# design.net
KiCad netlist of a schematic drawn in Altium Designer
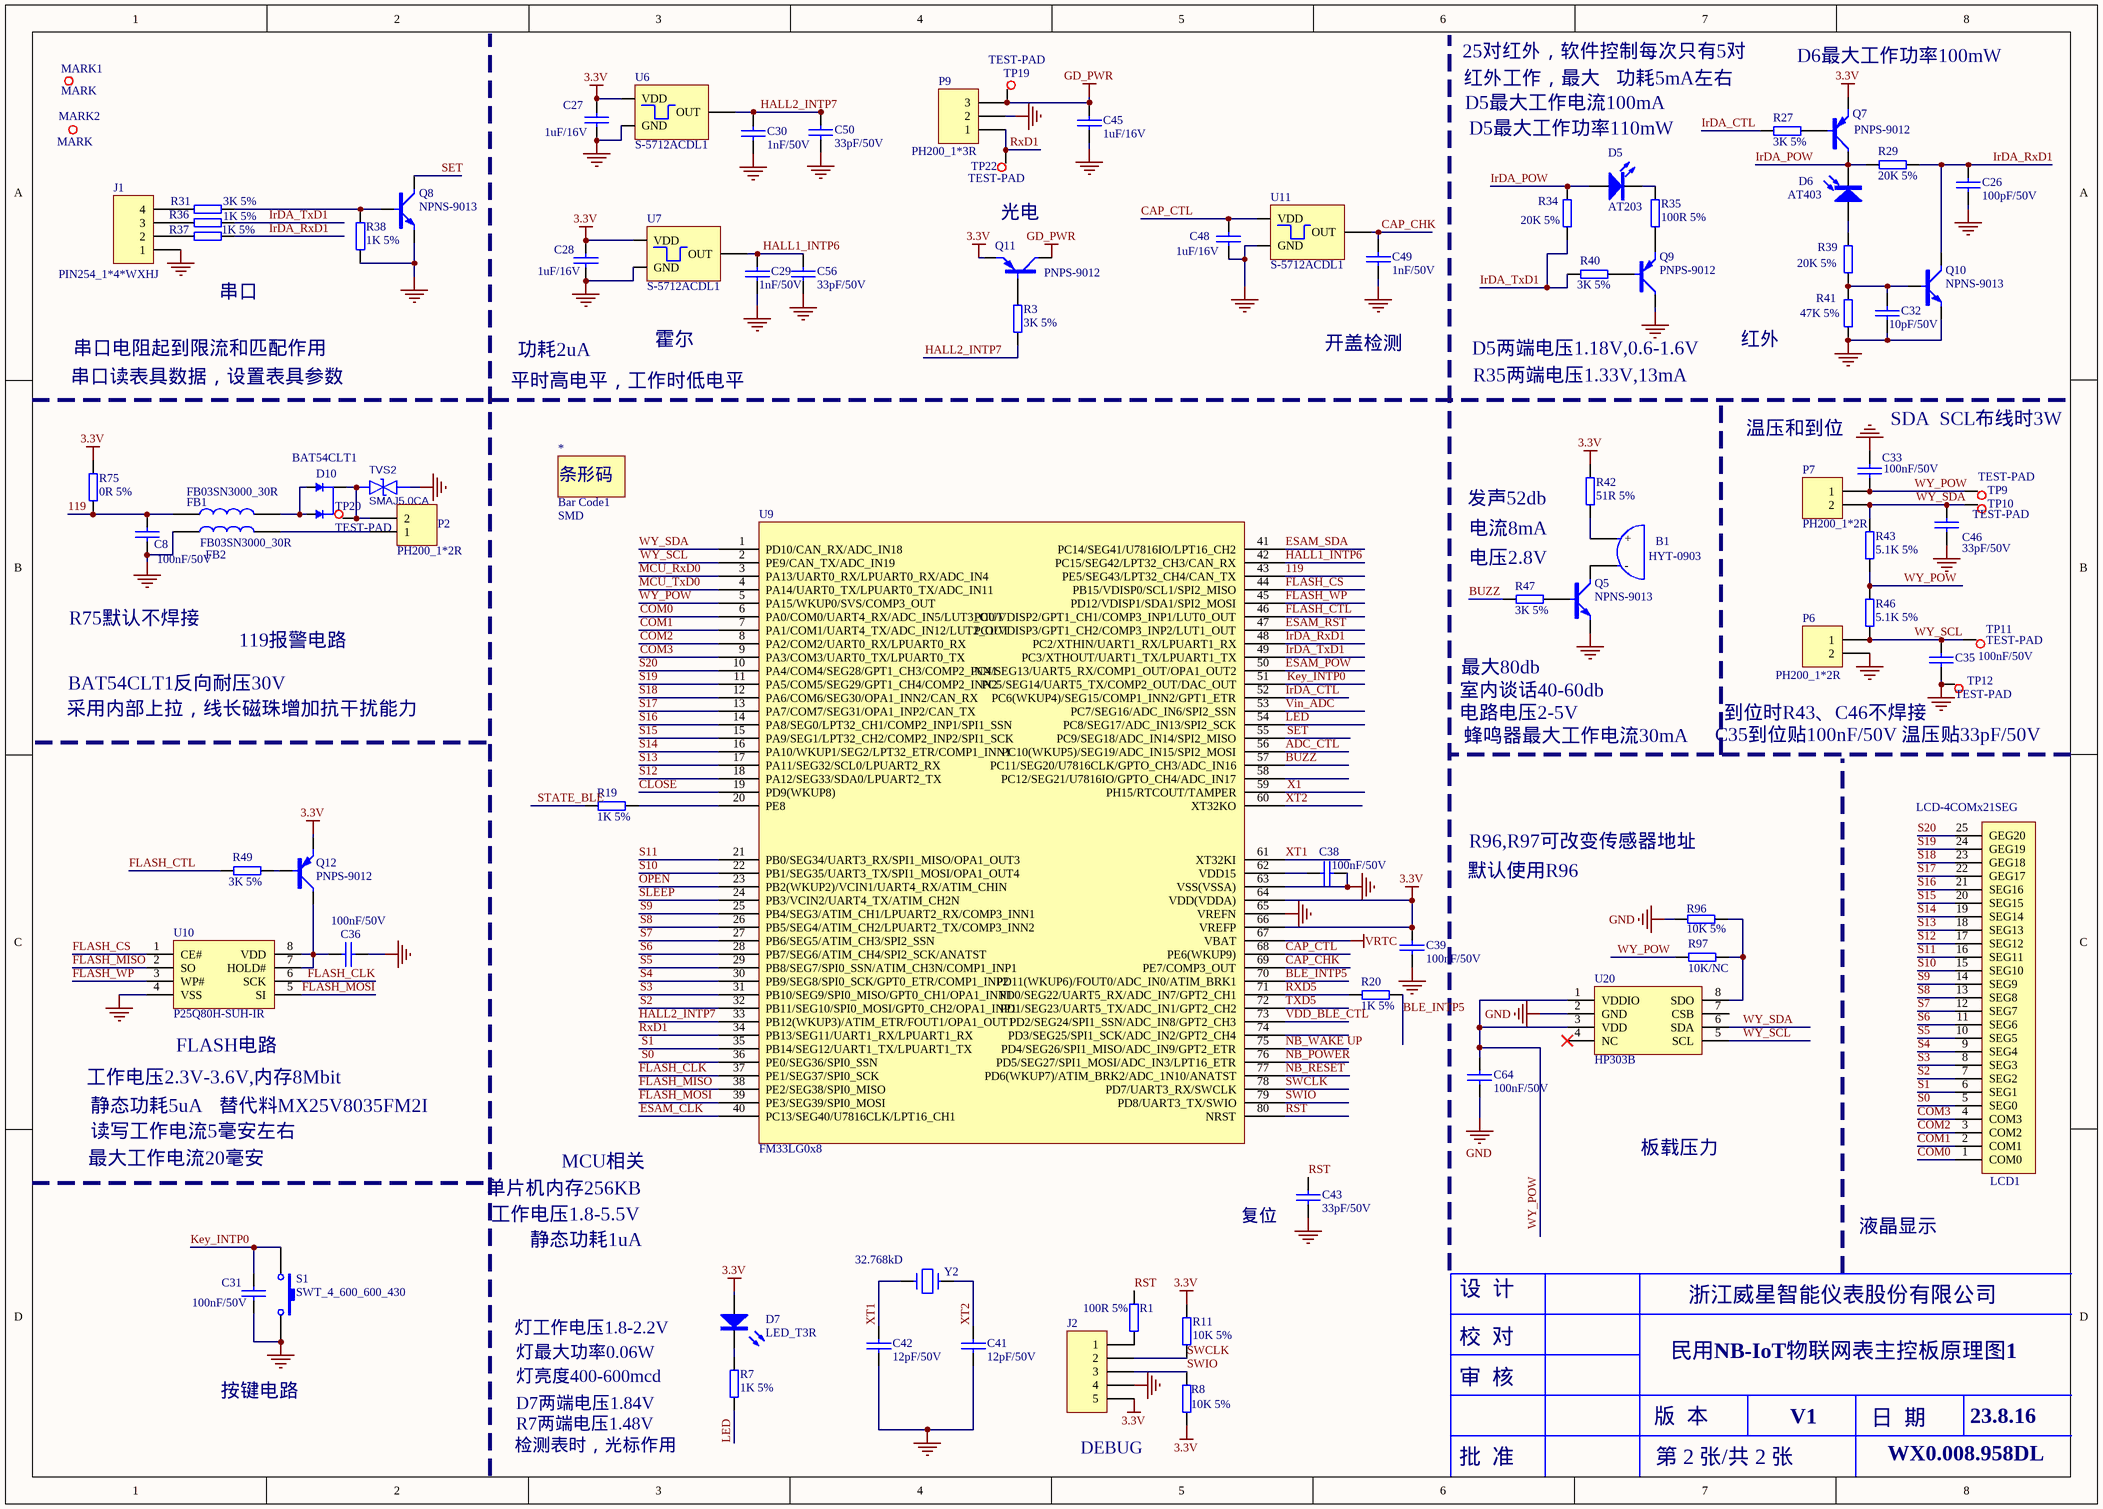
[diagram p0: 主控板.SchDoc]

(export (version "E")
  (design (tool "Eeschema 10.0.6"))
  (components
    (comp (ref "*")
      (value "Bar Code1")
      (footprint "Bar Code1")
      (description "条形码 ,填充，无需焊接器件")
      (fields (field (name "PART NUMBER") "AD_WXHJ_Bar Code_02") (field (name "SMD/DIP") "SMD"))
      (libsource (lib "Database_Libs2") (part "05_AD_WXHJ_Bar Code_02"))
    )
    (comp (ref "B1")
      (value "HYT-0903")
      (footprint "HYT-0903")
      (description "直插,直径9mm,高5.5mm,5 V,2 V,30 mA,兴化市华宇电子有限公司,HYT-0903")
      (fields (field (name "PART NUMBER") "1010602-0007"))
      (libsource (lib "Database_Libs2") (part "07_HYT-0903"))
    )
    (comp (ref "C8")
      (value "100nF/50V")
      (footprint "CAP0603")
      (description "104pF,50 V,±10%,0603,国巨,CC0603KRX7R9BB104")
      (fields (field (name "PART NUMBER") "101020103-0021"))
      (libsource (lib "Database_Libs2") (part "CC03K7R9_100N"))
    )
    (comp (ref "C26")
      (value "100pF/50V")
      (footprint "CAP0603")
      (description "101pf,50 V,±5%,0603,国巨,CC0603JRNP09BN101")
      (fields (field (name "PART NUMBER") "101020103-0010"))
      (libsource (lib "Database_Libs2") (part "CC03JPO9_101P"))
    )
    (comp (ref "C27")
      (value "1uF/16V")
      (footprint "CAP0603")
      (description "105pF,16 V,±10%,0603,国巨,CC0603KRX7R7BB105")
      (fields (field (name "PART NUMBER") "101020103-0003"))
      (libsource (lib "Database_Libs2") (part "CC03K7R7_1U"))
    )
    (comp (ref "C28")
      (value "1uF/16V")
      (footprint "CAP0603")
      (description "105pF,16 V,±10%,0603,国巨,CC0603KRX7R7BB105")
      (fields (field (name "PART NUMBER") "101020103-0003"))
      (libsource (lib "Database_Libs2") (part "CC03K7R7_1U"))
    )
    (comp (ref "C29")
      (value "1nF/50V")
      (footprint "CAP0603")
      (description "102pF,50 V,±10%,0603,国巨,CC0603KRX7R9BB102")
      (fields (field (name "PART NUMBER") "101020103-0022"))
      (libsource (lib "Database_Libs2") (part "CC03K7R9_1N"))
    )
    (comp (ref "C30")
      (value "1nF/50V")
      (footprint "CAP0603")
      (description "102pF,50 V,±10%,0603,国巨,CC0603KRX7R9BB102")
      (fields (field (name "PART NUMBER") "101020103-0022"))
      (libsource (lib "Database_Libs2") (part "CC03K7R9_1N"))
    )
    (comp (ref "C31")
      (value "100nF/50V")
      (footprint "CAP0603")
      (description "104pF,50 V,±10%,0603,国巨,CC0603KRX7R9BB104")
      (fields (field (name "PART NUMBER") "101020103-0021"))
      (libsource (lib "Database_Libs2") (part "CC03K7R9_100N"))
    )
    (comp (ref "C32")
      (value "10pF/50V")
      (footprint "CAP0603")
      (description "10pF,50 V,±5%,0603,X7R,国巨,CC0603JRNPO9BN100")
      (fields (field (name "PART NUMBER") "101020103-0014"))
      (libsource (lib "Database_Libs2") (part "CC03JPO9_10P"))
    )
    (comp (ref "C33")
      (value "100nF/50V")
      (footprint "CAP0603")
      (description "104pF,50 V,±10%,0603,国巨,CC0603KRX7R9BB104")
      (fields (field (name "PART NUMBER") "101020103-0021"))
      (libsource (lib "Database_Libs2") (part "CC03K7R9_100N"))
    )
    (comp (ref "C35")
      (value "100nF/50V")
      (footprint "CAP0603")
      (description "104pF,50 V,±10%,0603,国巨,CC0603KRX7R9BB104")
      (fields (field (name "PART NUMBER") "101020103-0021"))
      (libsource (lib "Database_Libs2") (part "CC03K7R9_100N"))
    )
    (comp (ref "C36")
      (value "100nF/50V")
      (footprint "CAP0603")
      (description "104pF,50 V,±10%,0603,国巨,CC0603KRX7R9BB104")
      (fields (field (name "PART NUMBER") "101020103-0021"))
      (libsource (lib "Database_Libs2") (part "CC03K7R9_100N"))
    )
    (comp (ref "C38")
      (value "100nF/50V")
      (footprint "CAP0603")
      (description "104pF,50 V,±10%,0603,国巨,CC0603KRX7R9BB104")
      (fields (field (name "PART NUMBER") "101020103-0021"))
      (libsource (lib "Database_Libs2") (part "CC03K7R9_100N"))
    )
    (comp (ref "C39")
      (value "100nF/50V")
      (footprint "CAP0603")
      (description "104pF,50 V,±10%,0603,国巨,CC0603KRX7R9BB104")
      (fields (field (name "PART NUMBER") "101020103-0021"))
      (libsource (lib "Database_Libs2") (part "CC03K7R9_100N"))
    )
    (comp (ref "C41")
      (value "12pF/50V")
      (footprint "CAP0603")
      (description "12P,50 V,±5%,0603,国巨,CC0603JRNPO9BN12")
      (fields (field (name "PART NUMBER") "101020103-0005"))
      (libsource (lib "Database_Libs2") (part "CC03JPO9_12P"))
    )
    (comp (ref "C42")
      (value "12pF/50V")
      (footprint "CAP0603")
      (description "12P,50 V,±5%,0603,国巨,CC0603JRNPO9BN12")
      (fields (field (name "PART NUMBER") "101020103-0005"))
      (libsource (lib "Database_Libs2") (part "CC03JPO9_12P"))
    )
    (comp (ref "C43")
      (value "33pF/50V")
      (footprint "CAP0603")
      (description "33pF,50 V,±10%,0603,国巨,CC0603KRNPO9BN33")
      (fields (field (name "PART NUMBER") "101020103-0027"))
      (libsource (lib "Database_Libs2") (part "CC03KPO9_33P"))
    )
    (comp (ref "C45")
      (value "1uF/16V")
      (footprint "CAP0603")
      (description "105pF,16 V,±10%,0603,国巨,CC0603KRX7R7BB105")
      (fields (field (name "PART NUMBER") "101020103-0003"))
      (libsource (lib "Database_Libs2") (part "CC03K7R7_1U"))
    )
    (comp (ref "C46")
      (value "33pF/50V")
      (footprint "CAP0603")
      (description "33pF,50 V,±10%,0603,国巨,CC0603KRNPO9BN33")
      (fields (field (name "PART NUMBER") "101020103-0027"))
      (libsource (lib "Database_Libs2") (part "CC03KPO9_33P"))
    )
    (comp (ref "C48")
      (value "1uF/16V")
      (footprint "CAP0603")
      (description "105pF,16 V,±10%,0603,国巨,CC0603KRX7R7BB105")
      (fields (field (name "PART NUMBER") "101020103-0003"))
      (libsource (lib "Database_Libs2") (part "CC03K7R7_1U"))
    )
    (comp (ref "C49")
      (value "1nF/50V")
      (footprint "CAP0603")
      (description "102pF,50 V,±10%,0603,国巨,CC0603KRX7R9BB102")
      (fields (field (name "PART NUMBER") "101020103-0022"))
      (libsource (lib "Database_Libs2") (part "CC03K7R9_1N"))
    )
    (comp (ref "C50")
      (value "33pF/50V")
      (footprint "CAP0603")
      (description "33pF,50 V,±10%,0603,国巨,CC0603KRNPO9BN33")
      (fields (field (name "PART NUMBER") "101020103-0027"))
      (libsource (lib "Database_Libs2") (part "CC03KPO9_33P"))
    )
    (comp (ref "C56")
      (value "33pF/50V")
      (footprint "CAP0603")
      (description "33pF,50 V,±10%,0603,国巨,CC0603KRNPO9BN33")
      (fields (field (name "PART NUMBER") "101020103-0027"))
      (libsource (lib "Database_Libs2") (part "CC03KPO9_33P"))
    )
    (comp (ref "C64")
      (value "100nF/50V")
      (footprint "CAP0603")
      (description "104pF,50 V,±10%,0603,国巨,CC0603KRX7R9BB104")
      (fields (field (name "PART NUMBER") "101020103-0021"))
      (libsource (lib "Database_Libs2") (part "CC03K7R9_100N"))
    )
    (comp (ref "D5")
      (value "AT203")
      (footprint "IR_254_532_300")
      (description "DIP-2,φ3,插件,红光,上海品观电子有限公司/可得,AT203")
      (fields (field (name "PART NUMBER") "101040102-0010"))
      (libsource (lib "Database_Libs2") (part "01_AT203"))
    )
    (comp (ref "D6")
      (value "AT403")
      (footprint "IR_254_532_300")
      (description "DIP-2,φ3,插件,红光,上海品观电子有限公司/可得,AT403-PD-01")
      (fields (field (name "PART NUMBER") "101040102-0011"))
      (libsource (lib "Database_Libs2") (part "01_AT403"))
    )
    (comp (ref "D7")
      (value "LED_T3R")
      (footprint "LED2_300")
      (description "圆形插件,3mm 圆形,插件,红光,湖北匡通电子有限公司,3BB4HC")
      (fields (field (name "PART NUMBER") "101040102-0001"))
      (libsource (lib "Database_Libs2") (part "01-LED_T3R"))
    )
    (comp (ref "D10")
      (value "BAT54CLT1")
      (footprint "SOT-23")
      (description "BAT54CLT1，SOT23-3,SOT23-3,0.2 A,0.8 V,30 V,安森美,BAT54CLT1")
      (fields (field (name "PART NUMBER") "101040101-0038"))
      (libsource (lib "Database_Libs2") (part "02_BAT54CLT1"))
    )
    (comp (ref "FB1")
      (value "FB03SN3000_30R")
      (footprint "IND0603")
      (description "chilisin(奇力新),0603,30Ω ±25% @100MHz,150 V,125 ℃,PBY160808T-300Y-N,-55 ℃,不含铅,,,圆盘,30Ω ±25% @100MHz")
      (fields (field (name "PART NUMBER") "109010101-0003"))
      (libsource (lib "Database_Libs2") (part "06_FB03SN3000_30R"))
    )
    (comp (ref "FB2")
      (value "FB03SN3000_30R")
      (footprint "IND0603")
      (description "chilisin(奇力新),0603,30Ω ±25% @100MHz,150 V,125 ℃,PBY160808T-300Y-N,-55 ℃,不含铅,,,圆盘,30Ω ±25% @100MHz")
      (fields (field (name "PART NUMBER") "109010101-0003"))
      (libsource (lib "Database_Libs2") (part "06_FB03SN3000_30R"))
    )
    (comp (ref "J1")
      (value "PIN254_1*4*WXHJ")
      (footprint "PIN254_1*4*WXHJ")
      (description "1*4 ，Φ1.0 ，2.54mm，直脚,无需焊接器件")
      (fields (field (name "PART NUMBER") "AD_WXHJ_PinHeader_01"))
      (libsource (lib "Database_Libs2") (part "PIN254_1*4*WXHJ"))
    )
    (comp (ref "J2")
      (value "PIN254_1*5*WXHJ")
      (footprint "PIN254_1*5*WXHJ")
      (description "1*5 ，Φ1.0 ，2.54mm，直脚,无需焊接器件")
      (fields (field (name "PART NUMBER") "AD_WXHJ_PinHeader_02"))
      (libsource (lib "Database_Libs2") (part "PIN254_1*5*WXHJ"))
    )
    (comp (ref "LCD1")
      (value "GVH21861A-HPP")
      (footprint "LCD_GVH21861A-HPP")
      (fields (field (name "PART NUMBER") "1010801-0028") (field (name "SMD/DIP") "LCD-4COMx21SEG"))
      (libsource (lib "Database_Libs2") (part "03_LCD_GVH21861A-HPP"))
    )
    (comp (ref "MARK1")
      (value "MARK")
      (footprint "MARK")
      (description "MARK点")
      (fields (field (name "PART NUMBER") "AD_WXHJ_MARK_01"))
      (libsource (lib "Database_Libs2") (part "MARK"))
    )
    (comp (ref "MARK2")
      (value "MARK")
      (footprint "MARK")
      (description "MARK点")
      (fields (field (name "PART NUMBER") "AD_WXHJ_MARK_01"))
      (libsource (lib "Database_Libs2") (part "MARK"))
    )
    (comp (ref "P2")
      (value "PH200_1*2R")
      (footprint "PH200_1*2R")
      (description "2.0-2AW,直插弯座，2PIN，脚间距2mm，带防翘起,公头,单排,2.0-2AW;直插弯座，2PIN,脚间距2mm，带防翘起")
      (fields (field (name "PART NUMBER") "1010902-0105"))
      (libsource (lib "Database_Libs2") (part "PH200_1*2R"))
    )
    (comp (ref "P6")
      (value "PH200_1*2R")
      (footprint "PH200_1*2R")
      (description "2.0-2AW,直插弯座，2PIN，脚间距2mm，带防翘起,公头,单排,2.0-2AW;直插弯座，2PIN,脚间距2mm，带防翘起")
      (fields (field (name "PART NUMBER") "1010902-0105"))
      (libsource (lib "") (part "PH200_1*2R_1"))
    )
    (comp (ref "P7")
      (value "PH200_1*2R")
      (footprint "PH200_1*2R")
      (description "2.0-2AW,直插弯座，2PIN，脚间距2mm，带防翘起,公头,单排,2.0-2AW;直插弯座，2PIN,脚间距2mm，带防翘起")
      (fields (field (name "PART NUMBER") "1010902-0105"))
      (libsource (lib "") (part "PH200_1*2R_1"))
    )
    (comp (ref "P9")
      (value "PH200_1*3R")
      (footprint "PH200_1*3R")
      (description "2.0-3AW,3PIN，2mm脚间距,公头,单排,2.0-3AW；3PIN，脚间距2mm直插弯座带防翘起")
      (fields (field (name "PART NUMBER") "1010902-0104"))
      (libsource (lib "Database_Libs2") (part "PH200_1*3R"))
    )
    (comp (ref "Q5")
      (value "NPNS-9013")
      (footprint "SOT-23")
      (description "9013,NPN,SOT-23,长电,S9013")
      (fields (field (name "PART NUMBER") "101040201-0002"))
      (libsource (lib "Database_Libs2") (part "03_NPNS-9013"))
    )
    (comp (ref "Q7")
      (value "PNPS-9012")
      (footprint "SOT-23")
      (description "9012,PNP,SOT-23,JCET;长电,S9012")
      (fields (field (name "PART NUMBER") "101040201-0001"))
      (libsource (lib "Database_Libs2") (part "03_PNPS-9012"))
    )
    (comp (ref "Q8")
      (value "NPNS-9013")
      (footprint "SOT-23")
      (description "9013,NPN,SOT-23,长电,S9013")
      (fields (field (name "PART NUMBER") "101040201-0002"))
      (libsource (lib "Database_Libs2") (part "03_NPNS-9013"))
    )
    (comp (ref "Q9")
      (value "PNPS-9012")
      (footprint "SOT-23")
      (description "9012,PNP,SOT-23,JCET;长电,S9012")
      (fields (field (name "PART NUMBER") "101040201-0001"))
      (libsource (lib "Database_Libs2") (part "03_PNPS-9012"))
    )
    (comp (ref "Q10")
      (value "NPNS-9013")
      (footprint "SOT-23")
      (description "9013,NPN,SOT-23,长电,S9013")
      (fields (field (name "PART NUMBER") "101040201-0002"))
      (libsource (lib "Database_Libs2") (part "03_NPNS-9013"))
    )
    (comp (ref "Q11")
      (value "PNPS-9012")
      (footprint "SOT-23")
      (description "9012,PNP,SOT-23,JCET;长电,S9012")
      (fields (field (name "PART NUMBER") "101040201-0001"))
      (libsource (lib "Database_Libs2") (part "03_PNPS-9012"))
    )
    (comp (ref "Q12")
      (value "PNPS-9012")
      (footprint "SOT-23")
      (description "9012,PNP,SOT-23,JCET;长电,S9012")
      (fields (field (name "PART NUMBER") "101040201-0001"))
      (libsource (lib "Database_Libs2") (part "03_PNPS-9012"))
    )
    (comp (ref "R1")
      (value "100R 5%")
      (footprint "RES0603")
      (description "100R,±5%,1/10W,0603,国巨,RC0603JR-07100RL")
      (fields (field (name "PART NUMBER") "101010103-0022"))
      (libsource (lib "Database_Libs2") (part "RC03J_100R"))
    )
    (comp (ref "R3")
      (value "3K 5%")
      (footprint "RES0603")
      (description "国巨,±5%,0603,,155 ℃,-55 ℃,RC0603JR-073KL,无铅,100 ppm/℃,1/10W,,3K")
      (fields (field (name "PART NUMBER") "101010103-0006"))
      (libsource (lib "Database_Libs2") (part "RC03J_3K"))
    )
    (comp (ref "R7")
      (value "1K 5%")
      (footprint "RES0603")
      (description "1K,±5%,1/10W,0603,国巨,RC0603JR-071KL")
      (fields (field (name "PART NUMBER") "101010103-0008"))
      (libsource (lib "Database_Libs2") (part "RC03J_1K"))
    )
    (comp (ref "R8")
      (value "10K 5%")
      (footprint "RES0603")
      (description "国巨,±5%,0603,,155 ℃,-55 ℃,RC0603JR-0710KL,无铅,200 ppm/℃,1/10W,,10K")
      (fields (field (name "PART NUMBER") "101010103-0003"))
      (libsource (lib "Database_Libs2") (part "RC03J_10K"))
    )
    (comp (ref "R11")
      (value "10K 5%")
      (footprint "RES0603")
      (description "国巨,±5%,0603,,155 ℃,-55 ℃,RC0603JR-0710KL,无铅,200 ppm/℃,1/10W,,10K")
      (fields (field (name "PART NUMBER") "101010103-0003"))
      (libsource (lib "Database_Libs2") (part "RC03J_10K"))
    )
    (comp (ref "R19")
      (value "1K 5%")
      (footprint "RES0603")
      (description "1K,±5%,1/10W,0603,国巨,RC0603JR-071KL")
      (fields (field (name "PART NUMBER") "101010103-0008"))
      (libsource (lib "Database_Libs2") (part "RC03J_1K"))
    )
    (comp (ref "R20")
      (value "1K 5%")
      (footprint "RES0603")
      (description "1K,±5%,1/10W,0603,国巨,RC0603JR-071KL")
      (fields (field (name "PART NUMBER") "101010103-0008"))
      (libsource (lib "Database_Libs2") (part "RC03J_1K"))
    )
    (comp (ref "R27")
      (value "3K 5%")
      (footprint "RES0603")
      (description "国巨,±5%,0603,,155 ℃,-55 ℃,RC0603JR-073KL,无铅,100 ppm/℃,1/10W,,3K")
      (fields (field (name "PART NUMBER") "101010103-0006"))
      (libsource (lib "Database_Libs2") (part "RC03J_3K"))
    )
    (comp (ref "R29")
      (value "20K 5%")
      (footprint "RES0603")
      (description "国巨,±5%,0603,,155 ℃,-55 ℃,RC0603JR-0720KL,无铅,200 ppm/℃,1/10W,,20K")
      (fields (field (name "PART NUMBER") "101010103-0004"))
      (libsource (lib "Database_Libs2") (part "RC03J_20K"))
    )
    (comp (ref "R31")
      (value "3K 5%")
      (footprint "RES0603")
      (description "国巨,±5%,0603,,155 ℃,-55 ℃,RC0603JR-073KL,无铅,100 ppm/℃,1/10W,,3K")
      (fields (field (name "PART NUMBER") "101010103-0006"))
      (libsource (lib "Database_Libs2") (part "RC03J_3K"))
    )
    (comp (ref "R34")
      (value "20K 5%")
      (footprint "RES0603")
      (description "国巨,±5%,0603,,155 ℃,-55 ℃,RC0603JR-0720KL,无铅,200 ppm/℃,1/10W,,20K")
      (fields (field (name "PART NUMBER") "101010103-0004"))
      (libsource (lib "Database_Libs2") (part "RC03J_20K"))
    )
    (comp (ref "R35")
      (value "100R 5%")
      (footprint "RES0603")
      (description "100R,±5%,1/10W,0603,国巨,RC0603JR-07100RL")
      (fields (field (name "PART NUMBER") "101010103-0022"))
      (libsource (lib "Database_Libs2") (part "RC03J_100R"))
    )
    (comp (ref "R36")
      (value "1K 5%")
      (footprint "RES0603")
      (description "1K,±5%,1/10W,0603,国巨,RC0603JR-071KL")
      (fields (field (name "PART NUMBER") "101010103-0008"))
      (libsource (lib "Database_Libs2") (part "RC03J_1K"))
    )
    (comp (ref "R37")
      (value "1K 5%")
      (footprint "RES0603")
      (description "1K,±5%,1/10W,0603,国巨,RC0603JR-071KL")
      (fields (field (name "PART NUMBER") "101010103-0008"))
      (libsource (lib "Database_Libs2") (part "RC03J_1K"))
    )
    (comp (ref "R38")
      (value "1K 5%")
      (footprint "RES0603")
      (description "1K,±5%,1/10W,0603,国巨,RC0603JR-071KL")
      (fields (field (name "PART NUMBER") "101010103-0008"))
      (libsource (lib "Database_Libs2") (part "RC03J_1K"))
    )
    (comp (ref "R39")
      (value "20K 5%")
      (footprint "RES0603")
      (description "国巨,±5%,0603,,155 ℃,-55 ℃,RC0603JR-0720KL,无铅,200 ppm/℃,1/10W,,20K")
      (fields (field (name "PART NUMBER") "101010103-0004"))
      (libsource (lib "Database_Libs2") (part "RC03J_20K"))
    )
    (comp (ref "R40")
      (value "3K 5%")
      (footprint "RES0603")
      (description "国巨,±5%,0603,,155 ℃,-55 ℃,RC0603JR-073KL,无铅,100 ppm/℃,1/10W,,3K")
      (fields (field (name "PART NUMBER") "101010103-0006"))
      (libsource (lib "Database_Libs2") (part "RC03J_3K"))
    )
    (comp (ref "R41")
      (value "47K 5%")
      (footprint "RES0603")
      (description "47K,±5%,1/10W,0603,国巨,RC0603JR-0747KL")
      (fields (field (name "PART NUMBER") "101010103-0012"))
      (libsource (lib "Database_Libs2") (part "RC03J_47K"))
    )
    (comp (ref "R42")
      (value "51R 5%")
      (footprint "RES0603")
      (description "国巨,±5%,0603,,155 ℃,-55 ℃,RC0603JR-0751RL,无铅,100 ppm/℃,1/10W,,51欧")
      (fields (field (name "PART NUMBER") "101010103-0037"))
      (libsource (lib "Database_Libs2") (part "RC03J_51R"))
    )
    (comp (ref "R43")
      (value "5.1K 5%")
      (footprint "RES0603")
      (description "国巨,±5%,0603,,155 ℃,55 ℃,RC0603JR-075.1KL,无铅,200 ppm/℃,1/10W,,5.1k")
      (fields (field (name "PART NUMBER") "101010103-0015"))
      (libsource (lib "Database_Libs2") (part "RC03J_5.1K"))
    )
    (comp (ref "R46")
      (value "5.1K 5%")
      (footprint "RES0603")
      (description "国巨,±5%,0603,,155 ℃,55 ℃,RC0603JR-075.1KL,无铅,200 ppm/℃,1/10W,,5.1k")
      (fields (field (name "PART NUMBER") "101010103-0015"))
      (libsource (lib "Database_Libs2") (part "RC03J_5.1K"))
    )
    (comp (ref "R47")
      (value "3K 5%")
      (footprint "RES0603")
      (description "国巨,±5%,0603,,155 ℃,-55 ℃,RC0603JR-073KL,无铅,100 ppm/℃,1/10W,,3K")
      (fields (field (name "PART NUMBER") "101010103-0006"))
      (libsource (lib "Database_Libs2") (part "RC03J_3K"))
    )
    (comp (ref "R49")
      (value "3K 5%")
      (footprint "RES0603")
      (description "国巨,±5%,0603,,155 ℃,-55 ℃,RC0603JR-073KL,无铅,100 ppm/℃,1/10W,,3K")
      (fields (field (name "PART NUMBER") "101010103-0006"))
      (libsource (lib "Database_Libs2") (part "RC03J_3K"))
    )
    (comp (ref "R75")
      (value "0R 5%")
      (footprint "RES0603")
      (description "国巨,±5%,0603,,155 ℃,-55 ℃,RC0603J2-070RL,无铅,200 ppm/℃,1/10W,,0R")
      (fields (field (name "PART NUMBER") "101010103-0001"))
      (libsource (lib "Database_Libs2") (part "RC03J_0R"))
    )
    (comp (ref "R96")
      (value "10K 5%")
      (footprint "RES0603")
      (description "国巨,±5%,0603,,155 ℃,-55 ℃,RC0603J2-070RL,无铅,200 ppm/℃,1/10W,,0R")
      (fields (field (name "PART NUMBER") "101010103-0001"))
      (libsource (lib "Database_Libs2") (part "RC03J_0R"))
    )
    (comp (ref "R97")
      (value "10K/NC")
      (footprint "RES0603")
      (description "国巨,±5%,0603,,155 ℃,-55 ℃,RC0603JR-071ML,无铅,200 ppm/℃,1/10W,,1M")
      (libsource (lib "Database_Libs2") (part "RC03J_1M"))
    )
    (comp (ref "S1")
      (value "SWT_4_600_600_430")
      (footprint "SWT_4_600_600")
      (description "TS-1102,机械轻触,6*6*4.3直插,6*6*4.3直插,乐清市羽欧电子")
      (fields (field (name "PART NUMBER") "1011001-0027"))
      (libsource (lib "Database_Libs2") (part "07_SWT_4_600_600_430"))
    )
    (comp (ref "TP9")
      (value "TEST-PAD")
      (footprint "TEST-PAD")
      (description "单面焊盘测试点")
      (fields (field (name "PART NUMBER") "AD_WXHJ_TEST-PAD_01"))
      (libsource (lib "Database_Libs2") (part "TEST-PAD"))
    )
    (comp (ref "TP10")
      (value "TEST-PAD")
      (footprint "TEST-PAD")
      (description "单面焊盘测试点")
      (fields (field (name "PART NUMBER") "AD_WXHJ_TEST-PAD_01"))
      (libsource (lib "Database_Libs2") (part "TEST-PAD"))
    )
    (comp (ref "TP11")
      (value "TEST-PAD")
      (footprint "TEST-PAD")
      (description "单面焊盘测试点")
      (fields (field (name "PART NUMBER") "AD_WXHJ_TEST-PAD_01"))
      (libsource (lib "Database_Libs2") (part "TEST-PAD"))
    )
    (comp (ref "TP12")
      (value "TEST-PAD")
      (footprint "TEST-PAD")
      (description "单面焊盘测试点")
      (fields (field (name "PART NUMBER") "AD_WXHJ_TEST-PAD_01"))
      (libsource (lib "Database_Libs2") (part "TEST-PAD"))
    )
    (comp (ref "TP19")
      (value "TEST-PAD")
      (footprint "TEST-PAD")
      (description "单面焊盘测试点")
      (fields (field (name "PART NUMBER") "AD_WXHJ_TEST-PAD_01"))
      (libsource (lib "Database_Libs2") (part "TEST-PAD"))
    )
    (comp (ref "TP20")
      (value "TEST-PAD")
      (footprint "TEST-PAD")
      (description "单面焊盘测试点")
      (fields (field (name "PART NUMBER") "AD_WXHJ_TEST-PAD_01"))
      (libsource (lib "Database_Libs2") (part "TEST-PAD"))
    )
    (comp (ref "TP22")
      (value "TEST-PAD")
      (footprint "TEST-PAD")
      (description "单面焊盘测试点")
      (fields (field (name "PART NUMBER") "AD_WXHJ_TEST-PAD_01"))
      (libsource (lib "Database_Libs2") (part "TEST-PAD"))
    )
    (comp (ref "TVS2")
      (value "SMAJ5.0CA")
      (footprint "SMAJ5.0CA")
      (fields (field (name "BOM_SUPPLIER PART") "C693487") (field (name "CONTRIBUTOR") "LCSC"))
      (libsource (lib "Discrete_WX") (part "SMAJ5.0CA_C693487"))
    )
    (comp (ref "U6")
      (value "S-5712ACDL1")
      (footprint "SOT-23")
      (description "S-5712ACDL1,SOT23-3,3.5 V,1.6 V,2 uA,精工电子,S-5712ACDL1")
      (fields (field (name "PART NUMBER") "1010504-0002"))
      (libsource (lib "Database_Libs2") (part "01_S-5712ACDL1"))
    )
    (comp (ref "U7")
      (value "S-5712ACDL1")
      (footprint "SOT-23")
      (description "S-5712ACDL1,SOT23-3,3.5 V,1.6 V,2 uA,精工电子,S-5712ACDL1")
      (fields (field (name "PART NUMBER") "1010504-0002"))
      (libsource (lib "Database_Libs2") (part "01_S-5712ACDL1"))
    )
    (comp (ref "U9") (value "FM33LG0x8") (footprint "LQFP80") (libsource (lib "FM_MCU") (part "FM33LG0x8")))
    (comp (ref "U10")
      (value "P25Q80H-SUH-IR")
      (footprint "SOP-8L-200MIL")
      (description "P25Q80H-SUH-IR,SOP8208mil,普冉半导体（上海）股份有限公司,P25Q80H-SUH-IR")
      (fields (field (name "PART NUMBER") "101050101-0218"))
      (libsource (lib "Database_Libs2") (part "04_GD25VQ80CSIG"))
    )
    (comp (ref "U11")
      (value "S-5712ACDL1")
      (footprint "SOT-23")
      (description "S-5712ACDL1,SOT23-3,3.5 V,1.6 V,2 uA,精工电子,S-5712ACDL1")
      (fields (field (name "PART NUMBER") "1010504-0002"))
      (libsource (lib "Database_Libs2") (part "01_S-5712ACDL1"))
    )
    (comp (ref "U20") (value "HP303B") (footprint "LGA_8") (libsource (lib "Schlib2") (part "HP303B")))
    (comp (ref "Y2")
      (value "32.768kD")
      (footprint "SMD-3215_2P")
      (fields (field (name "PART NUMBER") "1010601-0020"))
      (libsource (lib "Database_Libs2") (part "04_XTALSG12MD_32.768kD"))
    )
  )
  (nets
    (net (code "1") (name "/119") (class "Default")
      (node (ref "C8") (pin "1") (pinfunction "1_1") (pintype "passive"))
      (node (ref "FB1") (pin "1") (pinfunction "1_1") (pintype "passive"))
      (node (ref "R75") (pin "2") (pinfunction "2_2") (pintype "passive"))
      (node (ref "U9") (pin "43") (pinfunction "PE5/SEG43/LPT32_CH4/CAN_TX_43") (pintype "passive"))
    )
    (net (code "2") (name "/ADC_CTL") (class "Default")
      (node (ref "U9") (pin "56") (pinfunction "PC10(WKUP5)/SEG19/ADC_IN15/SPI2_MOSI_56") (pintype "passive"))
    )
    (net (code "3") (name "/BLE_INTP5") (class "Default")
      (node (ref "R20") (pin "1") (pinfunction "1_1") (pintype "passive"))
      (node (ref "U9") (pin "70") (pinfunction "PD11(WKUP6)/FOUT0/ADC_IN0/ATIM_BRK1_70") (pintype "passive"))
    )
    (net (code "4") (name "/BUZZ") (class "Default")
      (node (ref "R47") (pin "1") (pinfunction "1_1") (pintype "passive"))
      (node (ref "U9") (pin "57") (pinfunction "PC11/SEG20/U7816CLK/GPTO_CH3/ADC_IN16_57") (pintype "passive"))
    )
    (net (code "5") (name "/CAP_CHK") (class "Default")
      (node (ref "C49") (pin "1") (pinfunction "1_1") (pintype "passive"))
      (node (ref "U11") (pin "2") (pinfunction "OUT_2") (pintype "passive"))
      (node (ref "U9") (pin "69") (pinfunction "PE7/COMP3_OUT_69") (pintype "passive"))
    )
    (net (code "6") (name "/CAP_CTL") (class "Default")
      (node (ref "C48") (pin "1") (pinfunction "1_1") (pintype "passive"))
      (node (ref "U11") (pin "1") (pinfunction "VDD_1") (pintype "passive"))
      (node (ref "U9") (pin "68") (pinfunction "PE6(WKUP9)_68") (pintype "passive"))
    )
    (net (code "7") (name "/CLOSE") (class "Default")
      (node (ref "U9") (pin "19") (pinfunction "PD9(WKUP8)_19") (pintype "passive"))
    )
    (net (code "8") (name "/COM0") (class "Default")
      (node (ref "LCD1") (pin "1") (pinfunction "COM0_1") (pintype "passive"))
      (node (ref "U9") (pin "6") (pinfunction "PA0/COM0/UART4_RX/ADC_IN5/LUT3_OUT_6") (pintype "passive"))
    )
    (net (code "9") (name "/COM1") (class "Default")
      (node (ref "LCD1") (pin "2") (pinfunction "COM1_2") (pintype "passive"))
      (node (ref "U9") (pin "7") (pinfunction "PA1/COM1/UART4_TX/ADC_IN12/LUT2_OUT_7") (pintype "passive"))
    )
    (net (code "10") (name "/COM2") (class "Default")
      (node (ref "LCD1") (pin "3") (pinfunction "COM2_3") (pintype "passive"))
      (node (ref "U9") (pin "8") (pinfunction "PA2/COM2/UART0_RX/LPUART0_RX_8") (pintype "passive"))
    )
    (net (code "11") (name "/COM3") (class "Default")
      (node (ref "LCD1") (pin "4") (pinfunction "COM3_4") (pintype "passive"))
      (node (ref "U9") (pin "9") (pinfunction "PA3/COM3/UART0_TX/LPUART0_TX_9") (pintype "passive"))
    )
    (net (code "12") (name "/ESAM_CLK") (class "Default")
      (node (ref "U9") (pin "40") (pinfunction "PC13/SEG40/U7816CLK/LPT16_CH1_40") (pintype "passive"))
    )
    (net (code "13") (name "/ESAM_POW") (class "Default")
      (node (ref "U9") (pin "50") (pinfunction "PC4/SEG13/UART5_RX/COMP1_OUT/OPA1_OUT2_50") (pintype "passive"))
    )
    (net (code "14") (name "/ESAM_RST") (class "Default")
      (node (ref "U9") (pin "47") (pinfunction "PC1/VDISP3/GPT1_CH2/COMP3_INP2/LUT1_OUT_47") (pintype "passive"))
    )
    (net (code "15") (name "/ESAM_SDA") (class "Default")
      (node (ref "U9") (pin "41") (pinfunction "PC14/SEG41/U7816IO/LPT16_CH2_41") (pintype "passive"))
    )
    (net (code "16") (name "/FLASH_CLK") (class "Default")
      (node (ref "U10") (pin "6") (pinfunction "SCK_6") (pintype "passive"))
      (node (ref "U9") (pin "37") (pinfunction "PE1/SEG37/SPI0_SCK_37") (pintype "passive"))
    )
    (net (code "17") (name "/FLASH_CS") (class "Default")
      (node (ref "U10") (pin "1") (pinfunction "CE#_1") (pintype "passive"))
      (node (ref "U9") (pin "44") (pinfunction "PB15/VDISP0/SCL1/SPI2_MISO_44") (pintype "passive"))
    )
    (net (code "18") (name "/FLASH_CTL") (class "Default")
      (node (ref "R49") (pin "1") (pinfunction "1_1") (pintype "passive"))
      (node (ref "U9") (pin "46") (pinfunction "PC0/VDISP2/GPT1_CH1/COMP3_INP1/LUT0_OUT_46") (pintype "passive"))
    )
    (net (code "19") (name "/FLASH_MISO") (class "Default")
      (node (ref "U10") (pin "2") (pinfunction "SO_2") (pintype "passive"))
      (node (ref "U9") (pin "38") (pinfunction "PE2/SEG38/SPI0_MISO_38") (pintype "passive"))
    )
    (net (code "20") (name "/FLASH_MOSI") (class "Default")
      (node (ref "U10") (pin "5") (pinfunction "SI_5") (pintype "passive"))
      (node (ref "U9") (pin "39") (pinfunction "PE3/SEG39/SPI0_MOSI_39") (pintype "passive"))
    )
    (net (code "21") (name "/FLASH_WP") (class "Default")
      (node (ref "U10") (pin "3") (pinfunction "WP#_3") (pintype "passive"))
      (node (ref "U9") (pin "45") (pinfunction "PD12/VDISP1/SDA1/SPI2_MOSI_45") (pintype "passive"))
    )
    (net (code "22") (name "/HALL1_INTP6") (class "Default")
      (node (ref "C29") (pin "1") (pinfunction "1_1") (pintype "passive"))
      (node (ref "C56") (pin "1") (pinfunction "1_1") (pintype "passive"))
      (node (ref "U7") (pin "2") (pinfunction "OUT_2") (pintype "passive"))
      (node (ref "U9") (pin "42") (pinfunction "PC15/SEG42/LPT32_CH3/CAN_RX_42") (pintype "passive"))
    )
    (net (code "23") (name "/HALL2_INTP7") (class "Default")
      (node (ref "C30") (pin "1") (pinfunction "1_1") (pintype "passive"))
      (node (ref "C50") (pin "1") (pinfunction "1_1") (pintype "passive"))
      (node (ref "R3") (pin "1") (pinfunction "1_1") (pintype "passive"))
      (node (ref "U6") (pin "2") (pinfunction "OUT_2") (pintype "passive"))
      (node (ref "U9") (pin "33") (pinfunction "PB12(WKUP3)/ATIM_ETR/FOUT1/OPA1_OUT1_33") (pintype "passive"))
    )
    (net (code "24") (name "/IrDA_CTL") (class "Default")
      (node (ref "R27") (pin "1") (pinfunction "1_1") (pintype "passive"))
      (node (ref "U9") (pin "52") (pinfunction "PC6(WKUP4)/SEG15/COMP1_INN2/GPT1_ETR_52") (pintype "passive"))
    )
    (net (code "25") (name "/IrDA_POW") (class "Default")
      (node (ref "D5") (pin "1") (pinfunction "A_1") (pintype "passive"))
      (node (ref "D6") (pin "2") (pinfunction "K_2") (pintype "passive"))
      (node (ref "Q7") (pin "3") (pinfunction "C_3") (pintype "passive"))
      (node (ref "R29") (pin "1") (pinfunction "1_1") (pintype "passive"))
      (node (ref "R34") (pin "2") (pinfunction "2_2") (pintype "passive"))
    )
    (net (code "26") (name "/IrDA_RxD1") (class "Default")
      (node (ref "C26") (pin "1") (pinfunction "1_1") (pintype "passive"))
      (node (ref "Q10") (pin "3") (pinfunction "C_3") (pintype "passive"))
      (node (ref "R29") (pin "2") (pinfunction "2_2") (pintype "passive"))
      (node (ref "R37") (pin "2") (pinfunction "2_2") (pintype "passive"))
      (node (ref "U9") (pin "48") (pinfunction "PC2/XTHIN/UART1_RX/LPUART1_RX_48") (pintype "passive"))
    )
    (net (code "27") (name "/IrDA_TxD1") (class "Default")
      (node (ref "R34") (pin "1") (pinfunction "1_1") (pintype "passive"))
      (node (ref "R36") (pin "2") (pinfunction "2_2") (pintype "passive"))
      (node (ref "R40") (pin "1") (pinfunction "1_1") (pintype "passive"))
      (node (ref "U9") (pin "49") (pinfunction "PC3/XTHOUT/UART1_TX/LPUART1_TX_49") (pintype "passive"))
    )
    (net (code "28") (name "/Key_INTP0") (class "Default")
      (node (ref "C31") (pin "1") (pinfunction "1_1") (pintype "passive"))
      (node (ref "S1") (pin "1") (pinfunction "1_1") (pintype "passive"))
      (node (ref "U9") (pin "51") (pinfunction "PC5/SEG14/UART5_TX/COMP2_OUT/DAC_OUT_51") (pintype "passive"))
    )
    (net (code "29") (name "/LED") (class "Default")
      (node (ref "R7") (pin "1") (pinfunction "1_1") (pintype "passive"))
      (node (ref "U9") (pin "54") (pinfunction "PC8/SEG17/ADC_IN13/SPI2_SCK_54") (pintype "passive"))
    )
    (net (code "30") (name "/MCU_RxD0") (class "Default")
      (node (ref "U9") (pin "3") (pinfunction "PA13/UART0_RX/LPUART0_RX/ADC_IN4_3") (pintype "passive"))
    )
    (net (code "31") (name "/MCU_TxD0") (class "Default")
      (node (ref "U9") (pin "4") (pinfunction "PA14/UART0_TX/LPUART0_TX/ADC_IN11_4") (pintype "passive"))
    )
    (net (code "32") (name "/NB_POWER") (class "Default")
      (node (ref "U9") (pin "76") (pinfunction "PD5/SEG27/SPI1_MOSI/ADC_IN3/LPT16_ETR_76") (pintype "passive"))
    )
    (net (code "33") (name "/NB_RESET") (class "Default")
      (node (ref "U9") (pin "77") (pinfunction "PD6(WKUP7)/ATIM_BRK2/ADC_1N10/ANATST_77") (pintype "passive"))
    )
    (net (code "34") (name "/NB_WAKE UP") (class "Default")
      (node (ref "U9") (pin "75") (pinfunction "PD4/SEG26/SPI1_MISO/ADC_IN9/GPT2_ETR_75") (pintype "passive"))
    )
    (net (code "35") (name "/OPEN") (class "Default")
      (node (ref "U9") (pin "23") (pinfunction "PB2(WKUP2)/VCIN1/UART4_RX/ATIM_CHIN_23") (pintype "passive"))
    )
    (net (code "36") (name "/RST") (class "Default")
      (node (ref "C43") (pin "1") (pinfunction "1_1") (pintype "passive"))
      (node (ref "R1") (pin "1") (pinfunction "1_1") (pintype "passive"))
      (node (ref "U9") (pin "80") (pinfunction "NRST_80") (pintype "passive"))
    )
    (net (code "37") (name "/RXD5") (class "Default")
      (node (ref "R20") (pin "2") (pinfunction "2_2") (pintype "passive"))
      (node (ref "U9") (pin "71") (pinfunction "PD0/SEG22/UART5_RX/ADC_IN7/GPT2_CH1_71") (pintype "passive"))
    )
    (net (code "38") (name "/RxD1") (class "Default")
      (node (ref "P9") (pin "1") (pinfunction "1_1") (pintype "passive"))
      (node (ref "TP22") (pin "1") (pinfunction "1_1") (pintype "passive"))
      (node (ref "U9") (pin "34") (pinfunction "PB13/SEG11/UART1_RX/LPUART1_RX_34") (pintype "passive"))
    )
    (net (code "39") (name "/S0") (class "Default")
      (node (ref "LCD1") (pin "5") (pinfunction "SEG0_5") (pintype "passive"))
      (node (ref "U9") (pin "36") (pinfunction "PE0/SEG36/SPI0_SSN_36") (pintype "passive"))
    )
    (net (code "40") (name "/S1") (class "Default")
      (node (ref "LCD1") (pin "6") (pinfunction "SEG1_6") (pintype "passive"))
      (node (ref "U9") (pin "35") (pinfunction "PB14/SEG12/UART1_TX/LPUART1_TX_35") (pintype "passive"))
    )
    (net (code "41") (name "/S2") (class "Default")
      (node (ref "LCD1") (pin "7") (pinfunction "SEG2_7") (pintype "passive"))
      (node (ref "U9") (pin "32") (pinfunction "PB11/SEG10/SPI0_MOSI/GPT0_CH2/OPA1_INP1_32") (pintype "passive"))
    )
    (net (code "42") (name "/S3") (class "Default")
      (node (ref "LCD1") (pin "8") (pinfunction "SEG3_8") (pintype "passive"))
      (node (ref "U9") (pin "31") (pinfunction "PB10/SEG9/SPI0_MISO/GPT0_CH1/OPA1_INN1_31") (pintype "passive"))
    )
    (net (code "43") (name "/S4") (class "Default")
      (node (ref "LCD1") (pin "9") (pinfunction "SEG4_9") (pintype "passive"))
      (node (ref "U9") (pin "30") (pinfunction "PB9/SEG8/SPI0_SCK/GPT0_ETR/COMP1_INP2_30") (pintype "passive"))
    )
    (net (code "44") (name "/S5") (class "Default")
      (node (ref "LCD1") (pin "10") (pinfunction "SEG5_10") (pintype "passive"))
      (node (ref "U9") (pin "29") (pinfunction "PB8/SEG7/SPI0_SSN/ATIM_CH3N/COMP1_INP1_29") (pintype "passive"))
    )
    (net (code "45") (name "/S6") (class "Default")
      (node (ref "LCD1") (pin "11") (pinfunction "SEG6_11") (pintype "passive"))
      (node (ref "U9") (pin "28") (pinfunction "PB7/SEG6/ATIM_CH4/SPI2_SCK/ANATST_28") (pintype "passive"))
    )
    (net (code "46") (name "/S7") (class "Default")
      (node (ref "LCD1") (pin "12") (pinfunction "SEG7_12") (pintype "passive"))
      (node (ref "U9") (pin "27") (pinfunction "PB6/SEG5/ATIM_CH3/SPI2_SSN_27") (pintype "passive"))
    )
    (net (code "47") (name "/S8") (class "Default")
      (node (ref "LCD1") (pin "13") (pinfunction "SEG8_13") (pintype "passive"))
      (node (ref "U9") (pin "26") (pinfunction "PB5/SEG4/ATIM_CH2/LPUART2_TX/COMP3_INN2_26") (pintype "passive"))
    )
    (net (code "48") (name "/S9") (class "Default")
      (node (ref "LCD1") (pin "14") (pinfunction "SEG9_14") (pintype "passive"))
      (node (ref "U9") (pin "25") (pinfunction "PB4/SEG3/ATIM_CH1/LPUART2_RX/COMP3_INN1_25") (pintype "passive"))
    )
    (net (code "49") (name "/S10") (class "Default")
      (node (ref "LCD1") (pin "15") (pinfunction "SEG10_15") (pintype "passive"))
      (node (ref "U9") (pin "22") (pinfunction "PB1/SEG35/UART3_TX/SPI1_MOSI/OPA1_OUT4_22") (pintype "passive"))
    )
    (net (code "50") (name "/S11") (class "Default")
      (node (ref "LCD1") (pin "16") (pinfunction "SEG11_16") (pintype "passive"))
      (node (ref "U9") (pin "21") (pinfunction "PB0/SEG34/UART3_RX/SPI1_MISO/OPA1_OUT3_21") (pintype "passive"))
    )
    (net (code "51") (name "/S12") (class "Default")
      (node (ref "LCD1") (pin "17") (pinfunction "SEG12_17") (pintype "passive"))
      (node (ref "U9") (pin "18") (pinfunction "PA12/SEG33/SDA0/LPUART2_TX_18") (pintype "passive"))
    )
    (net (code "52") (name "/S13") (class "Default")
      (node (ref "LCD1") (pin "18") (pinfunction "SEG13_18") (pintype "passive"))
      (node (ref "U9") (pin "17") (pinfunction "PA11/SEG32/SCL0/LPUART2_RX_17") (pintype "passive"))
    )
    (net (code "53") (name "/S14") (class "Default")
      (node (ref "LCD1") (pin "19") (pinfunction "SEG14_19") (pintype "passive"))
      (node (ref "U9") (pin "16") (pinfunction "PA10/WKUP1/SEG2/LPT32_ETR/COMP1_INN1_16") (pintype "passive"))
    )
    (net (code "54") (name "/S15") (class "Default")
      (node (ref "LCD1") (pin "20") (pinfunction "SEG15_20") (pintype "passive"))
      (node (ref "U9") (pin "15") (pinfunction "PA9/SEG1/LPT32_CH2/COMP2_INP2/SPI1_SCK_15") (pintype "passive"))
    )
    (net (code "55") (name "/S16") (class "Default")
      (node (ref "LCD1") (pin "21") (pinfunction "SEG16_21") (pintype "passive"))
      (node (ref "U9") (pin "14") (pinfunction "PA8/SEG0/LPT32_CH1/COMP2_INP1/SPI1_SSN_14") (pintype "passive"))
    )
    (net (code "56") (name "/S17") (class "Default")
      (node (ref "LCD1") (pin "22") (pinfunction "GEG17_22") (pintype "passive"))
      (node (ref "U9") (pin "13") (pinfunction "PA7/COM7/SEG31/OPA1_INP2/CAN_TX_13") (pintype "passive"))
    )
    (net (code "57") (name "/S18") (class "Default")
      (node (ref "LCD1") (pin "23") (pinfunction "GEG18_23") (pintype "passive"))
      (node (ref "U9") (pin "12") (pinfunction "PA6/COM6/SEG30/OPA1_INN2/CAN_RX_12") (pintype "passive"))
    )
    (net (code "58") (name "/S19") (class "Default")
      (node (ref "LCD1") (pin "24") (pinfunction "GEG19_24") (pintype "passive"))
      (node (ref "U9") (pin "11") (pinfunction "PA5/COM5/SEG29/GPT1_CH4/COMP2_INN2_11") (pintype "passive"))
    )
    (net (code "59") (name "/S20") (class "Default")
      (node (ref "LCD1") (pin "25") (pinfunction "GEG20_25") (pintype "passive"))
      (node (ref "U9") (pin "10") (pinfunction "PA4/COM4/SEG28/GPT1_CH3/COMP2_INN1_10") (pintype "passive"))
    )
    (net (code "60") (name "/SET") (class "Default")
      (node (ref "Q8") (pin "3") (pinfunction "C_3") (pintype "passive"))
      (node (ref "U9") (pin "55") (pinfunction "PC9/SEG18/ADC_IN14/SPI2_MISO_55") (pintype "passive"))
    )
    (net (code "61") (name "/SLEEP") (class "Default")
      (node (ref "U9") (pin "24") (pinfunction "PB3/VCIN2/UART4_TX/ATIM_CH2N_24") (pintype "passive"))
    )
    (net (code "62") (name "/STATE_BLE") (class "Default")
      (node (ref "R19") (pin "2") (pinfunction "2_2") (pintype "passive"))
    )
    (net (code "63") (name "/SWCLK") (class "Default")
      (node (ref "J2") (pin "2") (pinfunction "2_2") (pintype "passive"))
      (node (ref "R11") (pin "2") (pinfunction "2_2") (pintype "passive"))
      (node (ref "U9") (pin "78") (pinfunction "PD7/UART3_RX/SWCLK_78") (pintype "passive"))
    )
    (net (code "64") (name "/SWIO") (class "Default")
      (node (ref "J2") (pin "3") (pinfunction "3_3") (pintype "passive"))
      (node (ref "R8") (pin "2") (pinfunction "2_2") (pintype "passive"))
      (node (ref "U9") (pin "79") (pinfunction "PD8/UART3_TX/SWIO_79") (pintype "passive"))
    )
    (net (code "65") (name "/TXD5") (class "Default")
      (node (ref "U9") (pin "72") (pinfunction "PD1/SEG23/UART5_TX/ADC_IN1/GPT2_CH2_72") (pintype "passive"))
    )
    (net (code "66") (name "/VDD_BLE_CTL") (class "Default")
      (node (ref "U9") (pin "73") (pinfunction "PD2/SEG24/SPI1_SSN/ADC_IN8/GPT2_CH3_73") (pintype "passive"))
    )
    (net (code "67") (name "/Vin_ADC") (class "Default")
      (node (ref "U9") (pin "53") (pinfunction "PC7/SEG16/ADC_IN6/SPI2_SSN_53") (pintype "passive"))
    )
    (net (code "68") (name "/WY_POW") (class "Default")
      (node (ref "C33") (pin "2") (pinfunction "2_2") (pintype "passive"))
      (node (ref "C64") (pin "2") (pinfunction "2_2") (pintype "passive"))
      (node (ref "P7") (pin "1") (pinfunction "1_1") (pintype "passive"))
      (node (ref "R43") (pin "1") (pinfunction "1_1") (pintype "passive"))
      (node (ref "R46") (pin "2") (pinfunction "2_2") (pintype "passive"))
      (node (ref "R97") (pin "2") (pinfunction "2_2") (pintype "passive"))
      (node (ref "TP9") (pin "1") (pinfunction "1_1") (pintype "passive"))
      (node (ref "U20") (pin "1") (pinfunction "VDDIO_1") (pintype "passive"))
      (node (ref "U20") (pin "3") (pinfunction "VDD_3") (pintype "passive"))
      (node (ref "U9") (pin "5") (pinfunction "PA15/WKUP0/SVS/COMP3_OUT_5") (pintype "passive"))
    )
    (net (code "69") (name "/WY_SCL") (class "Default")
      (node (ref "C35") (pin "1") (pinfunction "1_1") (pintype "passive"))
      (node (ref "P6") (pin "1") (pinfunction "1_1") (pintype "passive"))
      (node (ref "R46") (pin "1") (pinfunction "1_1") (pintype "passive"))
      (node (ref "TP11") (pin "1") (pinfunction "1_1") (pintype "passive"))
      (node (ref "U20") (pin "5") (pinfunction "SCL_5") (pintype "passive"))
      (node (ref "U9") (pin "2") (pinfunction "PE9/CAN_TX/ADC_IN19_2") (pintype "passive"))
    )
    (net (code "70") (name "/WY_SDA") (class "Default")
      (node (ref "C46") (pin "1") (pinfunction "1_1") (pintype "passive"))
      (node (ref "P7") (pin "2") (pinfunction "2_2") (pintype "passive"))
      (node (ref "R43") (pin "2") (pinfunction "2_2") (pintype "passive"))
      (node (ref "TP10") (pin "1") (pinfunction "1_1") (pintype "passive"))
      (node (ref "U20") (pin "6") (pinfunction "SDA_6") (pintype "passive"))
      (node (ref "U9") (pin "1") (pinfunction "PD10/CAN_RX/ADC_IN18_1") (pintype "passive"))
    )
    (net (code "71") (name "/X1") (class "Default")
      (node (ref "U9") (pin "59") (pinfunction "PH15/RTCOUT/TAMPER_59") (pintype "passive"))
    )
    (net (code "72") (name "/XT1") (class "Default")
      (node (ref "C42") (pin "1") (pinfunction "1_1") (pintype "passive"))
      (node (ref "U9") (pin "61") (pinfunction "XT32KI_61") (pintype "passive"))
      (node (ref "Y2") (pin "1") (pinfunction "1_1") (pintype "passive"))
    )
    (net (code "73") (name "/XT2") (class "Default")
      (node (ref "C41") (pin "2") (pinfunction "2_2") (pintype "passive"))
      (node (ref "U9") (pin "60") (pinfunction "XT32KO_60") (pintype "passive"))
      (node (ref "Y2") (pin "2") (pinfunction "2_2") (pintype "passive"))
    )
    (net (code "74") (name "3.3V") (class "Default")
      (node (ref "C27") (pin "1") (pinfunction "1_1") (pintype "passive"))
      (node (ref "C28") (pin "1") (pinfunction "1_1") (pintype "passive"))
      (node (ref "C39") (pin "2") (pinfunction "2_2") (pintype "passive"))
      (node (ref "D7") (pin "1") (pinfunction "1_1") (pintype "passive"))
      (node (ref "J2") (pin "5") (pinfunction "5_5") (pintype "passive"))
      (node (ref "Q11") (pin "2") (pinfunction "E_2") (pintype "passive"))
      (node (ref "Q12") (pin "2") (pinfunction "E_2") (pintype "passive"))
      (node (ref "Q7") (pin "2") (pinfunction "E_2") (pintype "passive"))
      (node (ref "R11") (pin "1") (pinfunction "1_1") (pintype "passive"))
      (node (ref "R42") (pin "2") (pinfunction "2_2") (pintype "passive"))
      (node (ref "R75") (pin "1") (pinfunction "1_1") (pintype "passive"))
      (node (ref "R8") (pin "1") (pinfunction "1_1") (pintype "passive"))
      (node (ref "U6") (pin "1") (pinfunction "VDD_1") (pintype "passive"))
      (node (ref "U7") (pin "1") (pinfunction "VDD_1") (pintype "passive"))
      (node (ref "U9") (pin "64") (pinfunction "VDD(VDDA)_64") (pintype "passive"))
      (node (ref "U9") (pin "66") (pinfunction "VREFP_66") (pintype "passive"))
    )
    (net (code "75") (name "GD_PWR") (class "Default")
      (node (ref "C45") (pin "1") (pinfunction "1_1") (pintype "passive"))
      (node (ref "P9") (pin "3") (pinfunction "3_3") (pintype "passive"))
      (node (ref "Q11") (pin "3") (pinfunction "C_3") (pintype "passive"))
      (node (ref "TP19") (pin "1") (pinfunction "1_1") (pintype "passive"))
    )
    (net (code "76") (name "GND") (class "Default")
      (node (ref "C26") (pin "2") (pinfunction "2_2") (pintype "passive"))
      (node (ref "C27") (pin "2") (pinfunction "2_2") (pintype "passive"))
      (node (ref "C28") (pin "2") (pinfunction "2_2") (pintype "passive"))
      (node (ref "C29") (pin "2") (pinfunction "2_2") (pintype "passive"))
      (node (ref "C30") (pin "2") (pinfunction "2_2") (pintype "passive"))
      (node (ref "C31") (pin "2") (pinfunction "2_2") (pintype "passive"))
      (node (ref "C32") (pin "2") (pinfunction "2_2") (pintype "passive"))
      (node (ref "C33") (pin "1") (pinfunction "1_1") (pintype "passive"))
      (node (ref "C35") (pin "2") (pinfunction "2_2") (pintype "passive"))
      (node (ref "C36") (pin "2") (pinfunction "2_2") (pintype "passive"))
      (node (ref "C38") (pin "2") (pinfunction "2_2") (pintype "passive"))
      (node (ref "C39") (pin "1") (pinfunction "1_1") (pintype "passive"))
      (node (ref "C41") (pin "1") (pinfunction "1_1") (pintype "passive"))
      (node (ref "C42") (pin "2") (pinfunction "2_2") (pintype "passive"))
      (node (ref "C43") (pin "2") (pinfunction "2_2") (pintype "passive"))
      (node (ref "C45") (pin "2") (pinfunction "2_2") (pintype "passive"))
      (node (ref "C46") (pin "2") (pinfunction "2_2") (pintype "passive"))
      (node (ref "C48") (pin "2") (pinfunction "2_2") (pintype "passive"))
      (node (ref "C49") (pin "2") (pinfunction "2_2") (pintype "passive"))
      (node (ref "C50") (pin "2") (pinfunction "2_2") (pintype "passive"))
      (node (ref "C56") (pin "2") (pinfunction "2_2") (pintype "passive"))
      (node (ref "C64") (pin "1") (pinfunction "1_1") (pintype "passive"))
      (node (ref "C8") (pin "2") (pinfunction "2_2") (pintype "passive"))
      (node (ref "FB2") (pin "1") (pinfunction "1_1") (pintype "passive"))
      (node (ref "J1") (pin "1") (pinfunction "1_1") (pintype "passive"))
      (node (ref "J2") (pin "4") (pinfunction "4_4") (pintype "passive"))
      (node (ref "P6") (pin "2") (pinfunction "2_2") (pintype "passive"))
      (node (ref "P9") (pin "2") (pinfunction "2_2") (pintype "passive"))
      (node (ref "Q10") (pin "2") (pinfunction "E_2") (pintype "passive"))
      (node (ref "Q5") (pin "2") (pinfunction "E_2") (pintype "passive"))
      (node (ref "Q8") (pin "2") (pinfunction "E_2") (pintype "passive"))
      (node (ref "Q9") (pin "3") (pinfunction "C_3") (pintype "passive"))
      (node (ref "R38") (pin "1") (pinfunction "1_1") (pintype "passive"))
      (node (ref "R41") (pin "1") (pinfunction "1_1") (pintype "passive"))
      (node (ref "R96") (pin "1") (pinfunction "1_1") (pintype "passive"))
      (node (ref "S1") (pin "2") (pinfunction "2_2") (pintype "passive"))
      (node (ref "TP12") (pin "1") (pinfunction "1_1") (pintype "passive"))
      (node (ref "TVS2") (pin "1") (pinfunction "1_1") (pintype "passive"))
      (node (ref "U10") (pin "4") (pinfunction "VSS_4") (pintype "passive"))
      (node (ref "U11") (pin "3") (pinfunction "GND_3") (pintype "passive"))
      (node (ref "U20") (pin "2") (pinfunction "GND_2") (pintype "passive"))
      (node (ref "U6") (pin "3") (pinfunction "GND_3") (pintype "passive"))
      (node (ref "U7") (pin "3") (pinfunction "GND_3") (pintype "passive"))
      (node (ref "U9") (pin "63") (pinfunction "VSS(VSSA)_63") (pintype "passive"))
      (node (ref "U9") (pin "65") (pinfunction "VREFN_65") (pintype "passive"))
    )
    (net (code "77") (name "Net-(B1-+)") (class "Default")
      (node (ref "B1") (pin "1") (pinfunction "+_1") (pintype "passive"))
      (node (ref "R42") (pin "1") (pinfunction "1_1") (pintype "passive"))
    )
    (net (code "78") (name "Net-(B1--)") (class "Default")
      (node (ref "B1") (pin "2") (pinfunction "-_2") (pintype "passive"))
      (node (ref "Q5") (pin "3") (pinfunction "C_3") (pintype "passive"))
    )
    (net (code "79") (name "Net-(D5-K)") (class "Default")
      (node (ref "D5") (pin "2") (pinfunction "K_2") (pintype "passive"))
      (node (ref "R35") (pin "2") (pinfunction "2_2") (pintype "passive"))
    )
    (net (code "80") (name "Net-(D6-A)") (class "Default")
      (node (ref "D6") (pin "1") (pinfunction "A_1") (pintype "passive"))
      (node (ref "R39") (pin "2") (pinfunction "2_2") (pintype "passive"))
    )
    (net (code "81") (name "Net-(D7-Pad2)") (class "Default")
      (node (ref "D7") (pin "2") (pinfunction "2_2") (pintype "passive"))
      (node (ref "R7") (pin "2") (pinfunction "2_2") (pintype "passive"))
    )
    (net (code "82") (name "Net-(D10-A-Pad1)") (class "Default")
      (node (ref "D10") (pin "1") (pinfunction "A_1") (pintype "passive"))
      (node (ref "D10") (pin "2") (pinfunction "A_2") (pintype "passive"))
      (node (ref "FB1") (pin "2") (pinfunction "2_2") (pintype "passive"))
    )
    (net (code "83") (name "Net-(D10-C)") (class "Default")
      (node (ref "D10") (pin "3") (pinfunction "C_3") (pintype "passive"))
      (node (ref "P2") (pin "2") (pinfunction "2_2") (pintype "passive"))
      (node (ref "TP20") (pin "1") (pinfunction "1_1") (pintype "passive"))
      (node (ref "TVS2") (pin "2") (pinfunction "2_2") (pintype "passive"))
    )
    (net (code "84") (name "Net-(FB2-Pad2)") (class "Default")
      (node (ref "FB2") (pin "2") (pinfunction "2_2") (pintype "passive"))
      (node (ref "P2") (pin "1") (pinfunction "1_1") (pintype "passive"))
    )
    (net (code "85") (name "Net-(J1-Pad2)") (class "Default")
      (node (ref "J1") (pin "2") (pinfunction "2_2") (pintype "passive"))
      (node (ref "R37") (pin "1") (pinfunction "1_1") (pintype "passive"))
    )
    (net (code "86") (name "Net-(J1-Pad3)") (class "Default")
      (node (ref "J1") (pin "3") (pinfunction "3_3") (pintype "passive"))
      (node (ref "R36") (pin "1") (pinfunction "1_1") (pintype "passive"))
    )
    (net (code "87") (name "Net-(J1-Pad4)") (class "Default")
      (node (ref "J1") (pin "4") (pinfunction "4_4") (pintype "passive"))
      (node (ref "R31") (pin "1") (pinfunction "1_1") (pintype "passive"))
    )
    (net (code "88") (name "Net-(J2-Pad1)") (class "Default")
      (node (ref "J2") (pin "1") (pinfunction "1_1") (pintype "passive"))
      (node (ref "R1") (pin "2") (pinfunction "2_2") (pintype "passive"))
    )
    (net (code "89") (name "Net-(Q5-B)") (class "Default")
      (node (ref "Q5") (pin "1") (pinfunction "B_1") (pintype "passive"))
      (node (ref "R47") (pin "2") (pinfunction "2_2") (pintype "passive"))
    )
    (net (code "90") (name "Net-(Q7-B)") (class "Default")
      (node (ref "Q7") (pin "1") (pinfunction "B_1") (pintype "passive"))
      (node (ref "R27") (pin "2") (pinfunction "2_2") (pintype "passive"))
    )
    (net (code "91") (name "Net-(Q8-B)") (class "Default")
      (node (ref "Q8") (pin "1") (pinfunction "B_1") (pintype "passive"))
      (node (ref "R31") (pin "2") (pinfunction "2_2") (pintype "passive"))
      (node (ref "R38") (pin "2") (pinfunction "2_2") (pintype "passive"))
    )
    (net (code "92") (name "Net-(Q9-B)") (class "Default")
      (node (ref "Q9") (pin "1") (pinfunction "B_1") (pintype "passive"))
      (node (ref "R40") (pin "2") (pinfunction "2_2") (pintype "passive"))
    )
    (net (code "93") (name "Net-(Q9-E)") (class "Default")
      (node (ref "Q9") (pin "2") (pinfunction "E_2") (pintype "passive"))
      (node (ref "R35") (pin "1") (pinfunction "1_1") (pintype "passive"))
    )
    (net (code "94") (name "Net-(Q10-B)") (class "Default")
      (node (ref "C32") (pin "1") (pinfunction "1_1") (pintype "passive"))
      (node (ref "Q10") (pin "1") (pinfunction "B_1") (pintype "passive"))
      (node (ref "R39") (pin "1") (pinfunction "1_1") (pintype "passive"))
      (node (ref "R41") (pin "2") (pinfunction "2_2") (pintype "passive"))
    )
    (net (code "95") (name "Net-(Q11-B)") (class "Default")
      (node (ref "Q11") (pin "1") (pinfunction "B_1") (pintype "passive"))
      (node (ref "R3") (pin "2") (pinfunction "2_2") (pintype "passive"))
    )
    (net (code "96") (name "Net-(Q12-B)") (class "Default")
      (node (ref "Q12") (pin "1") (pinfunction "B_1") (pintype "passive"))
      (node (ref "R49") (pin "2") (pinfunction "2_2") (pintype "passive"))
    )
    (net (code "97") (name "Net-(Q12-C)") (class "Default")
      (node (ref "C36") (pin "1") (pinfunction "1_1") (pintype "passive"))
      (node (ref "Q12") (pin "3") (pinfunction "C_3") (pintype "passive"))
      (node (ref "U10") (pin "7") (pinfunction "HOLD#_7") (pintype "passive"))
      (node (ref "U10") (pin "8") (pinfunction "VDD_8") (pintype "passive"))
    )
    (net (code "98") (name "Net-(U9-PE8)") (class "Default")
      (node (ref "R19") (pin "1") (pinfunction "1_1") (pintype "passive"))
      (node (ref "U9") (pin "20") (pinfunction "PE8_20") (pintype "passive"))
    )
    (net (code "99") (name "Net-(U9-VDD15)") (class "Default")
      (node (ref "C38") (pin "1") (pinfunction "1_1") (pintype "passive"))
      (node (ref "U9") (pin "62") (pinfunction "VDD15_62") (pintype "passive"))
    )
    (net (code "100") (name "Net-(U20-SDO)") (class "Default")
      (node (ref "R96") (pin "2") (pinfunction "2_2") (pintype "passive"))
      (node (ref "R97") (pin "1") (pinfunction "1_1") (pintype "passive"))
      (node (ref "U20") (pin "8") (pinfunction "SDO_8") (pintype "passive"))
    )
    (net (code "101") (name "VRTC") (class "Default")
      (node (ref "U9") (pin "67") (pinfunction "VBAT_67") (pintype "passive"))
    )
    (net (code "102") (name "unconnected-(U9-PC12{slash}SEG21{slash}U7816IO{slash}GPTO_CH4{slash}ADC_IN17-Pad58)") (class "Default")
      (node (ref "U9") (pin "58") (pinfunction "PC12/SEG21/U7816IO/GPTO_CH4/ADC_IN17_58") (pintype "passive"))
    )
    (net (code "103") (name "unconnected-(U9-PD3{slash}SEG25{slash}SPI1_SCK{slash}ADC_IN2{slash}GPT2_CH4-Pad74)") (class "Default")
      (node (ref "U9") (pin "74") (pinfunction "PD3/SEG25/SPI1_SCK/ADC_IN2/GPT2_CH4_74") (pintype "passive"))
    )
    (net (code "104") (name "unconnected-(U20-CSB-Pad7)") (class "Default")
      (node (ref "U20") (pin "7") (pinfunction "CSB_7") (pintype "passive"))
    )
    (net (code "105") (name "unconnected-(U20-NC-Pad4)") (class "Default")
      (node (ref "U20") (pin "4") (pinfunction "NC_4") (pintype "passive+no_connect"))
    )
  )
)
